# Arduino_MEGA_blank_shield.net
KiCad netlist of a schematic drawn in EAGLE
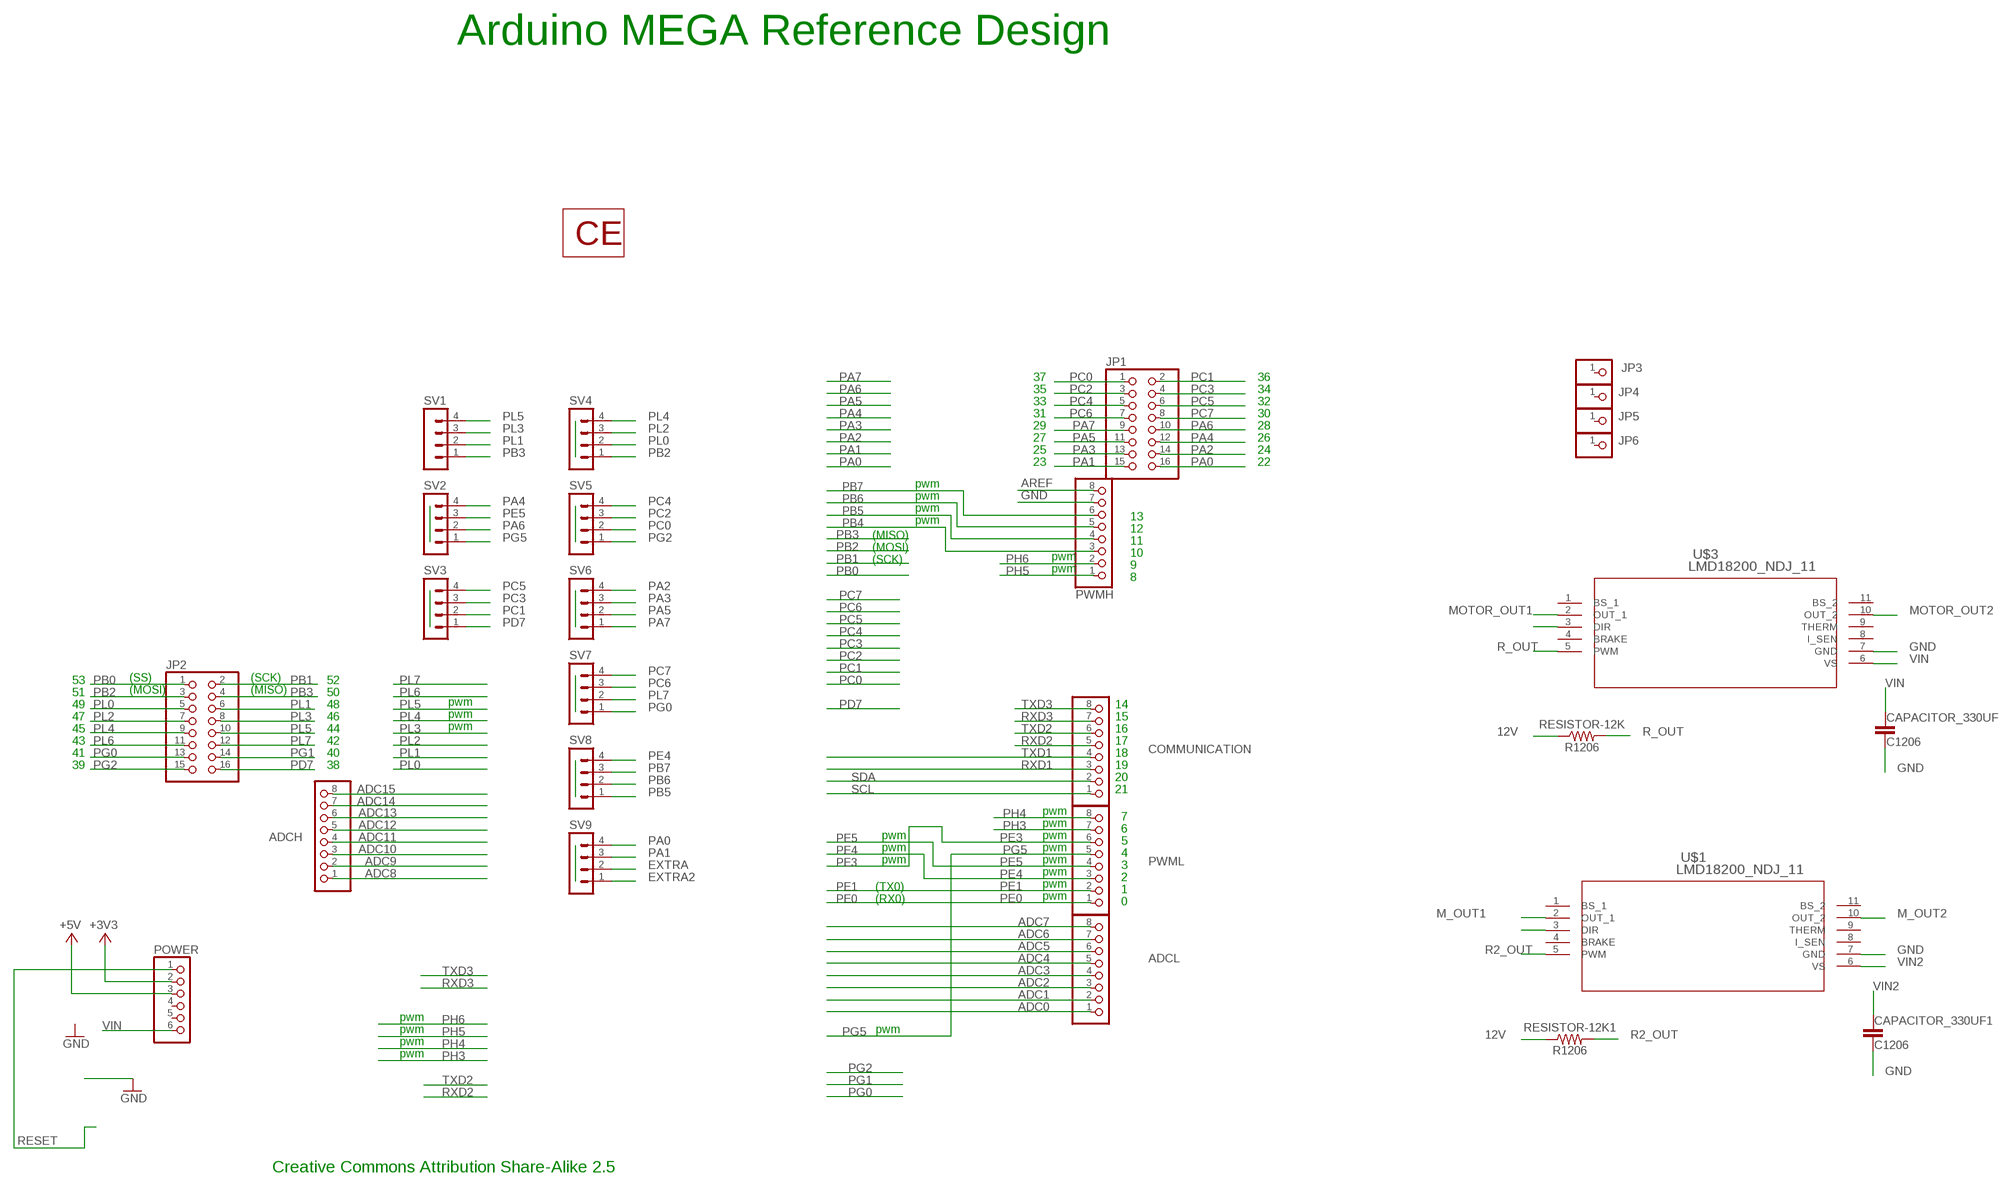
[diagram p0: schematic, sheet 1]

(export (version "E")
  (design (tool "Eeschema 10.0.6"))
  (components
    (comp (ref "ADCH")
      (value "PINHD-1X8")
      (footprint "eagle-import:1X08")
      (libsource (lib "eagle-import") (part "PINHD-1X8"))
    )
    (comp (ref "ADCL")
      (value "PINHD-1X8")
      (footprint "eagle-import:1X08")
      (libsource (lib "eagle-import") (part "PINHD-1X8"))
    )
    (comp (ref "CAPACITOR_330UF")
      (value "C1206")
      (footprint "eagle-import:C1206")
      (libsource (lib "eagle-import") (part "C1206"))
    )
    (comp (ref "CAPACITOR_330UF1")
      (value "C1206")
      (footprint "eagle-import:C1206")
      (libsource (lib "eagle-import") (part "C1206"))
    )
    (comp (ref "COMMUNICATION")
      (value "PINHD-1X8")
      (footprint "eagle-import:1X08")
      (libsource (lib "eagle-import") (part "PINHD-1X8"))
    )
    (comp (ref "JP1")
      (value "PINHD-2X8")
      (footprint "eagle-import:2X08")
      (libsource (lib "eagle-import") (part "PINHD-2X8"))
    )
    (comp (ref "JP2")
      (value "PINHD-2X8")
      (footprint "eagle-import:2X08")
      (libsource (lib "eagle-import") (part "PINHD-2X8"))
    )
    (comp (ref "JP3")
      (value "PINHD-1X1")
      (footprint "eagle-import:1X01")
      (libsource (lib "eagle-import") (part "PINHD-1X1"))
    )
    (comp (ref "JP4")
      (value "PINHD-1X1")
      (footprint "eagle-import:1X01")
      (libsource (lib "eagle-import") (part "PINHD-1X1"))
    )
    (comp (ref "JP5")
      (value "PINHD-1X1")
      (footprint "eagle-import:1X01")
      (libsource (lib "eagle-import") (part "PINHD-1X1"))
    )
    (comp (ref "JP6")
      (value "PINHD-1X1")
      (footprint "eagle-import:1X01")
      (libsource (lib "eagle-import") (part "PINHD-1X1"))
    )
    (comp (ref "POWER")
      (value "PINHD-1X6")
      (footprint "eagle-import:1X06")
      (libsource (lib "eagle-import") (part "PINHD-1X6"))
    )
    (comp (ref "PWMH")
      (value "PINHD-1X8")
      (footprint "eagle-import:1X08")
      (libsource (lib "eagle-import") (part "PINHD-1X8"))
    )
    (comp (ref "PWML")
      (value "PINHD-1X8")
      (footprint "eagle-import:1X08")
      (libsource (lib "eagle-import") (part "PINHD-1X8"))
    )
    (comp (ref "RESISTOR-12K")
      (value "R1206")
      (footprint "eagle-import:R1206")
      (libsource (lib "eagle-import") (part "R1206"))
    )
    (comp (ref "RESISTOR-12K1")
      (value "R1206")
      (footprint "eagle-import:R1206")
      (libsource (lib "eagle-import") (part "R1206"))
    )
    (comp (ref "SV1")
      (value "MA04-1")
      (footprint "eagle-import:MA04-1")
      (libsource (lib "eagle-import") (part "MA04-1"))
    )
    (comp (ref "SV2")
      (value "MA04-1")
      (footprint "eagle-import:MA04-1")
      (libsource (lib "eagle-import") (part "MA04-1"))
    )
    (comp (ref "SV3")
      (value "MA04-1")
      (footprint "eagle-import:MA04-1")
      (libsource (lib "eagle-import") (part "MA04-1"))
    )
    (comp (ref "SV4")
      (value "MA04-1")
      (footprint "eagle-import:MA04-1")
      (libsource (lib "eagle-import") (part "MA04-1"))
    )
    (comp (ref "SV5")
      (value "MA04-1")
      (footprint "eagle-import:MA04-1")
      (libsource (lib "eagle-import") (part "MA04-1"))
    )
    (comp (ref "SV6")
      (value "MA04-1")
      (footprint "eagle-import:MA04-1")
      (libsource (lib "eagle-import") (part "MA04-1"))
    )
    (comp (ref "SV7")
      (value "MA04-1")
      (footprint "eagle-import:MA04-1")
      (libsource (lib "eagle-import") (part "MA04-1"))
    )
    (comp (ref "SV8")
      (value "MA04-1")
      (footprint "eagle-import:MA04-1")
      (libsource (lib "eagle-import") (part "MA04-1"))
    )
    (comp (ref "SV9")
      (value "MA04-1")
      (footprint "eagle-import:MA04-1")
      (libsource (lib "eagle-import") (part "MA04-1"))
    )
    (comp (ref "U$1")
      (value "LMD18200_NDJ_11")
      (footprint "eagle-import:TA11B")
      (fields (field (name "MANUFACTURER_PART_NUMBER") "lmd18200tnopb"))
      (libsource (lib "eagle-import") (part "LMD18200_NDJ_11"))
    )
    (comp (ref "U$3")
      (value "LMD18200_NDJ_11")
      (footprint "eagle-import:TA11B")
      (fields (field (name "MANUFACTURER_PART_NUMBER") "lmd18200tnopb"))
      (libsource (lib "eagle-import") (part "LMD18200_NDJ_11"))
    )
    (comp (ref "U$4")
      (value "CE")
      (footprint "eagle-import:CE-COPPER")
      (libsource (lib "eagle-import") (part "CE"))
    )
  )
  (nets
    (net (code "1") (name "+3V3") (class "Default")
      (node (ref "POWER") (pin "2") (pinfunction "2_2") (pintype "passive"))
    )
    (net (code "2") (name "+5V") (class "Default")
      (node (ref "POWER") (pin "3") (pinfunction "3_3") (pintype "passive"))
    )
    (net (code "3") (name "/12V") (class "Default")
      (node (ref "RESISTOR-12K") (pin "1") (pinfunction "1_1") (pintype "passive"))
      (node (ref "RESISTOR-12K1") (pin "1") (pinfunction "1_1") (pintype "passive"))
    )
    (net (code "4") (name "/ADC0") (class "Default")
      (node (ref "ADCL") (pin "1") (pinfunction "1_1") (pintype "passive"))
    )
    (net (code "5") (name "/ADC1") (class "Default")
      (node (ref "ADCL") (pin "2") (pinfunction "2_2") (pintype "passive"))
    )
    (net (code "6") (name "/ADC2") (class "Default")
      (node (ref "ADCL") (pin "3") (pinfunction "3_3") (pintype "passive"))
    )
    (net (code "7") (name "/ADC3") (class "Default")
      (node (ref "ADCL") (pin "4") (pinfunction "4_4") (pintype "passive"))
    )
    (net (code "8") (name "/ADC4") (class "Default")
      (node (ref "ADCL") (pin "5") (pinfunction "5_5") (pintype "passive"))
    )
    (net (code "9") (name "/ADC5") (class "Default")
      (node (ref "ADCL") (pin "6") (pinfunction "6_6") (pintype "passive"))
    )
    (net (code "10") (name "/ADC6") (class "Default")
      (node (ref "ADCL") (pin "7") (pinfunction "7_7") (pintype "passive"))
    )
    (net (code "11") (name "/ADC7") (class "Default")
      (node (ref "ADCL") (pin "8") (pinfunction "8_8") (pintype "passive"))
    )
    (net (code "12") (name "/ADC8") (class "Default")
      (node (ref "ADCH") (pin "1") (pinfunction "1_1") (pintype "passive"))
    )
    (net (code "13") (name "/ADC9") (class "Default")
      (node (ref "ADCH") (pin "2") (pinfunction "2_2") (pintype "passive"))
    )
    (net (code "14") (name "/ADC10") (class "Default")
      (node (ref "ADCH") (pin "3") (pinfunction "3_3") (pintype "passive"))
    )
    (net (code "15") (name "/ADC11") (class "Default")
      (node (ref "ADCH") (pin "4") (pinfunction "4_4") (pintype "passive"))
    )
    (net (code "16") (name "/ADC12") (class "Default")
      (node (ref "ADCH") (pin "5") (pinfunction "5_5") (pintype "passive"))
    )
    (net (code "17") (name "/ADC13") (class "Default")
      (node (ref "ADCH") (pin "6") (pinfunction "6_6") (pintype "passive"))
    )
    (net (code "18") (name "/ADC14") (class "Default")
      (node (ref "ADCH") (pin "7") (pinfunction "7_7") (pintype "passive"))
    )
    (net (code "19") (name "/ADC15") (class "Default")
      (node (ref "ADCH") (pin "8") (pinfunction "8_8") (pintype "passive"))
    )
    (net (code "20") (name "/AREF") (class "Default")
      (node (ref "PWMH") (pin "8") (pinfunction "8_8") (pintype "passive"))
    )
    (net (code "21") (name "/EXTRA") (class "Default")
      (node (ref "SV9") (pin "2") (pinfunction "2_2") (pintype "passive"))
    )
    (net (code "22") (name "/EXTRA2") (class "Default")
      (node (ref "SV9") (pin "1") (pinfunction "1_1") (pintype "passive"))
    )
    (net (code "23") (name "/MOTOR_OUT1") (class "Default")
      (node (ref "U$3") (pin "2") (pinfunction "OUT_1_2") (pintype "output"))
    )
    (net (code "24") (name "/MOTOR_OUT2") (class "Default")
      (node (ref "U$3") (pin "10") (pinfunction "OUT_2_10") (pintype "output"))
    )
    (net (code "25") (name "/M_OUT1") (class "Default")
      (node (ref "U$1") (pin "2") (pinfunction "OUT_1_2") (pintype "output"))
    )
    (net (code "26") (name "/M_OUT2") (class "Default")
      (node (ref "U$1") (pin "10") (pinfunction "OUT_2_10") (pintype "output"))
    )
    (net (code "27") (name "/PA0") (class "Default")
      (node (ref "JP1") (pin "16") (pinfunction "16_16") (pintype "passive"))
      (node (ref "SV9") (pin "4") (pinfunction "4_4") (pintype "passive"))
    )
    (net (code "28") (name "/PA1") (class "Default")
      (node (ref "JP1") (pin "15") (pinfunction "15_15") (pintype "passive"))
      (node (ref "SV9") (pin "3") (pinfunction "3_3") (pintype "passive"))
    )
    (net (code "29") (name "/PA2") (class "Default")
      (node (ref "JP1") (pin "14") (pinfunction "14_14") (pintype "passive"))
      (node (ref "SV6") (pin "4") (pinfunction "4_4") (pintype "passive"))
    )
    (net (code "30") (name "/PA3") (class "Default")
      (node (ref "JP1") (pin "13") (pinfunction "13_13") (pintype "passive"))
      (node (ref "SV6") (pin "3") (pinfunction "3_3") (pintype "passive"))
    )
    (net (code "31") (name "/PA4") (class "Default")
      (node (ref "JP1") (pin "12") (pinfunction "12_12") (pintype "passive"))
      (node (ref "SV2") (pin "4") (pinfunction "4_4") (pintype "passive"))
    )
    (net (code "32") (name "/PA5") (class "Default")
      (node (ref "JP1") (pin "11") (pinfunction "11_11") (pintype "passive"))
      (node (ref "SV6") (pin "2") (pinfunction "2_2") (pintype "passive"))
    )
    (net (code "33") (name "/PA6") (class "Default")
      (node (ref "JP1") (pin "10") (pinfunction "10_10") (pintype "passive"))
      (node (ref "SV2") (pin "2") (pinfunction "2_2") (pintype "passive"))
    )
    (net (code "34") (name "/PA7") (class "Default")
      (node (ref "JP1") (pin "9") (pinfunction "9_9") (pintype "passive"))
      (node (ref "SV6") (pin "1") (pinfunction "1_1") (pintype "passive"))
    )
    (net (code "35") (name "/PB0") (class "Default")
      (node (ref "JP2") (pin "1") (pinfunction "1_1") (pintype "passive"))
    )
    (net (code "36") (name "/PB1") (class "Default")
      (node (ref "JP2") (pin "2") (pinfunction "2_2") (pintype "passive"))
    )
    (net (code "37") (name "/PB2") (class "Default")
      (node (ref "JP2") (pin "3") (pinfunction "3_3") (pintype "passive"))
      (node (ref "SV4") (pin "1") (pinfunction "1_1") (pintype "passive"))
    )
    (net (code "38") (name "/PB3") (class "Default")
      (node (ref "JP2") (pin "4") (pinfunction "4_4") (pintype "passive"))
      (node (ref "SV1") (pin "1") (pinfunction "1_1") (pintype "passive"))
    )
    (net (code "39") (name "/PB4") (class "Default")
      (node (ref "PWMH") (pin "3") (pinfunction "3_3") (pintype "passive"))
    )
    (net (code "40") (name "/PB5") (class "Default")
      (node (ref "PWMH") (pin "4") (pinfunction "4_4") (pintype "passive"))
      (node (ref "SV8") (pin "1") (pinfunction "1_1") (pintype "passive"))
    )
    (net (code "41") (name "/PB6") (class "Default")
      (node (ref "PWMH") (pin "5") (pinfunction "5_5") (pintype "passive"))
      (node (ref "SV8") (pin "2") (pinfunction "2_2") (pintype "passive"))
    )
    (net (code "42") (name "/PB7") (class "Default")
      (node (ref "PWMH") (pin "6") (pinfunction "6_6") (pintype "passive"))
      (node (ref "SV8") (pin "3") (pinfunction "3_3") (pintype "passive"))
    )
    (net (code "43") (name "/PC0") (class "Default")
      (node (ref "JP1") (pin "1") (pinfunction "1_1") (pintype "passive"))
      (node (ref "SV5") (pin "2") (pinfunction "2_2") (pintype "passive"))
    )
    (net (code "44") (name "/PC1") (class "Default")
      (node (ref "JP1") (pin "2") (pinfunction "2_2") (pintype "passive"))
      (node (ref "SV3") (pin "2") (pinfunction "2_2") (pintype "passive"))
    )
    (net (code "45") (name "/PC2") (class "Default")
      (node (ref "JP1") (pin "3") (pinfunction "3_3") (pintype "passive"))
      (node (ref "SV5") (pin "3") (pinfunction "3_3") (pintype "passive"))
    )
    (net (code "46") (name "/PC3") (class "Default")
      (node (ref "JP1") (pin "4") (pinfunction "4_4") (pintype "passive"))
      (node (ref "SV3") (pin "3") (pinfunction "3_3") (pintype "passive"))
    )
    (net (code "47") (name "/PC4") (class "Default")
      (node (ref "JP1") (pin "5") (pinfunction "5_5") (pintype "passive"))
      (node (ref "SV5") (pin "4") (pinfunction "4_4") (pintype "passive"))
    )
    (net (code "48") (name "/PC5") (class "Default")
      (node (ref "JP1") (pin "6") (pinfunction "6_6") (pintype "passive"))
      (node (ref "SV3") (pin "4") (pinfunction "4_4") (pintype "passive"))
    )
    (net (code "49") (name "/PC6") (class "Default")
      (node (ref "JP1") (pin "7") (pinfunction "7_7") (pintype "passive"))
      (node (ref "SV7") (pin "3") (pinfunction "3_3") (pintype "passive"))
    )
    (net (code "50") (name "/PC7") (class "Default")
      (node (ref "JP1") (pin "8") (pinfunction "8_8") (pintype "passive"))
      (node (ref "SV7") (pin "4") (pinfunction "4_4") (pintype "passive"))
    )
    (net (code "51") (name "/PD7") (class "Default")
      (node (ref "JP2") (pin "16") (pinfunction "16_16") (pintype "passive"))
      (node (ref "SV3") (pin "1") (pinfunction "1_1") (pintype "passive"))
    )
    (net (code "52") (name "/PE0") (class "Default")
      (node (ref "PWML") (pin "1") (pinfunction "1_1") (pintype "passive"))
    )
    (net (code "53") (name "/PE1") (class "Default")
      (node (ref "PWML") (pin "2") (pinfunction "2_2") (pintype "passive"))
    )
    (net (code "54") (name "/PE3") (class "Default")
      (node (ref "PWML") (pin "6") (pinfunction "6_6") (pintype "passive"))
    )
    (net (code "55") (name "/PE4") (class "Default")
      (node (ref "PWML") (pin "3") (pinfunction "3_3") (pintype "passive"))
      (node (ref "SV8") (pin "4") (pinfunction "4_4") (pintype "passive"))
    )
    (net (code "56") (name "/PE5") (class "Default")
      (node (ref "PWML") (pin "4") (pinfunction "4_4") (pintype "passive"))
      (node (ref "SV2") (pin "3") (pinfunction "3_3") (pintype "passive"))
    )
    (net (code "57") (name "/PG0") (class "Default")
      (node (ref "JP2") (pin "13") (pinfunction "13_13") (pintype "passive"))
      (node (ref "SV7") (pin "1") (pinfunction "1_1") (pintype "passive"))
    )
    (net (code "58") (name "/PG1") (class "Default")
      (node (ref "JP2") (pin "14") (pinfunction "14_14") (pintype "passive"))
    )
    (net (code "59") (name "/PG2") (class "Default")
      (node (ref "JP2") (pin "15") (pinfunction "15_15") (pintype "passive"))
      (node (ref "SV5") (pin "1") (pinfunction "1_1") (pintype "passive"))
    )
    (net (code "60") (name "/PG5") (class "Default")
      (node (ref "PWML") (pin "5") (pinfunction "5_5") (pintype "passive"))
      (node (ref "SV2") (pin "1") (pinfunction "1_1") (pintype "passive"))
    )
    (net (code "61") (name "/PH3") (class "Default")
      (node (ref "PWML") (pin "7") (pinfunction "7_7") (pintype "passive"))
    )
    (net (code "62") (name "/PH4") (class "Default")
      (node (ref "PWML") (pin "8") (pinfunction "8_8") (pintype "passive"))
    )
    (net (code "63") (name "/PH5") (class "Default")
      (node (ref "PWMH") (pin "1") (pinfunction "1_1") (pintype "passive"))
    )
    (net (code "64") (name "/PH6") (class "Default")
      (node (ref "PWMH") (pin "2") (pinfunction "2_2") (pintype "passive"))
    )
    (net (code "65") (name "/PL0") (class "Default")
      (node (ref "JP2") (pin "5") (pinfunction "5_5") (pintype "passive"))
      (node (ref "SV4") (pin "2") (pinfunction "2_2") (pintype "passive"))
    )
    (net (code "66") (name "/PL1") (class "Default")
      (node (ref "JP2") (pin "6") (pinfunction "6_6") (pintype "passive"))
      (node (ref "SV1") (pin "2") (pinfunction "2_2") (pintype "passive"))
    )
    (net (code "67") (name "/PL2") (class "Default")
      (node (ref "JP2") (pin "7") (pinfunction "7_7") (pintype "passive"))
      (node (ref "SV4") (pin "3") (pinfunction "3_3") (pintype "passive"))
    )
    (net (code "68") (name "/PL3") (class "Default")
      (node (ref "JP2") (pin "8") (pinfunction "8_8") (pintype "passive"))
      (node (ref "SV1") (pin "3") (pinfunction "3_3") (pintype "passive"))
    )
    (net (code "69") (name "/PL4") (class "Default")
      (node (ref "JP2") (pin "9") (pinfunction "9_9") (pintype "passive"))
      (node (ref "SV4") (pin "4") (pinfunction "4_4") (pintype "passive"))
    )
    (net (code "70") (name "/PL5") (class "Default")
      (node (ref "JP2") (pin "10") (pinfunction "10_10") (pintype "passive"))
      (node (ref "SV1") (pin "4") (pinfunction "4_4") (pintype "passive"))
    )
    (net (code "71") (name "/PL6") (class "Default")
      (node (ref "JP2") (pin "11") (pinfunction "11_11") (pintype "passive"))
    )
    (net (code "72") (name "/PL7") (class "Default")
      (node (ref "JP2") (pin "12") (pinfunction "12_12") (pintype "passive"))
      (node (ref "SV7") (pin "2") (pinfunction "2_2") (pintype "passive"))
    )
    (net (code "73") (name "/R2_OUT") (class "Default")
      (node (ref "RESISTOR-12K1") (pin "2") (pinfunction "2_2") (pintype "passive"))
      (node (ref "U$1") (pin "5") (pinfunction "PWM_5") (pintype "input"))
    )
    (net (code "74") (name "/RESET") (class "Default")
      (node (ref "POWER") (pin "1") (pinfunction "1_1") (pintype "passive"))
    )
    (net (code "75") (name "/RXD1") (class "Default")
      (node (ref "COMMUNICATION") (pin "3") (pinfunction "3_3") (pintype "passive"))
    )
    (net (code "76") (name "/RXD2") (class "Default")
      (node (ref "COMMUNICATION") (pin "5") (pinfunction "5_5") (pintype "passive"))
    )
    (net (code "77") (name "/RXD3") (class "Default")
      (node (ref "COMMUNICATION") (pin "7") (pinfunction "7_7") (pintype "passive"))
    )
    (net (code "78") (name "/R_OUT") (class "Default")
      (node (ref "RESISTOR-12K") (pin "2") (pinfunction "2_2") (pintype "passive"))
      (node (ref "U$3") (pin "5") (pinfunction "PWM_5") (pintype "input"))
    )
    (net (code "79") (name "/SCL") (class "Default")
      (node (ref "COMMUNICATION") (pin "1") (pinfunction "1_1") (pintype "passive"))
    )
    (net (code "80") (name "/SDA") (class "Default")
      (node (ref "COMMUNICATION") (pin "2") (pinfunction "2_2") (pintype "passive"))
    )
    (net (code "81") (name "/TXD1") (class "Default")
      (node (ref "COMMUNICATION") (pin "4") (pinfunction "4_4") (pintype "passive"))
    )
    (net (code "82") (name "/TXD2") (class "Default")
      (node (ref "COMMUNICATION") (pin "6") (pinfunction "6_6") (pintype "passive"))
    )
    (net (code "83") (name "/TXD3") (class "Default")
      (node (ref "COMMUNICATION") (pin "8") (pinfunction "8_8") (pintype "passive"))
    )
    (net (code "84") (name "/VIN") (class "Default")
      (node (ref "CAPACITOR_330UF") (pin "1") (pinfunction "1_1") (pintype "passive"))
      (node (ref "POWER") (pin "6") (pinfunction "6_6") (pintype "passive"))
      (node (ref "U$3") (pin "6") (pinfunction "VS_6") (pintype "power_in"))
    )
    (net (code "85") (name "/VIN2") (class "Default")
      (node (ref "CAPACITOR_330UF1") (pin "1") (pinfunction "1_1") (pintype "passive"))
      (node (ref "U$1") (pin "6") (pinfunction "VS_6") (pintype "power_in"))
    )
    (net (code "86") (name "GND") (class "Default")
      (node (ref "CAPACITOR_330UF") (pin "2") (pinfunction "2_2") (pintype "passive"))
      (node (ref "CAPACITOR_330UF1") (pin "2") (pinfunction "2_2") (pintype "passive"))
      (node (ref "PWMH") (pin "7") (pinfunction "7_7") (pintype "passive"))
      (node (ref "U$1") (pin "7") (pinfunction "GND_7") (pintype "power_in"))
      (node (ref "U$3") (pin "7") (pinfunction "GND_7") (pintype "power_in"))
    )
    (net (code "87") (name "unconnected-(JP3-Pad1)") (class "Default")
      (node (ref "JP3") (pin "1") (pinfunction "1_1") (pintype "passive"))
    )
    (net (code "88") (name "unconnected-(JP4-Pad1)") (class "Default")
      (node (ref "JP4") (pin "1") (pinfunction "1_1") (pintype "passive"))
    )
    (net (code "89") (name "unconnected-(JP5-Pad1)") (class "Default")
      (node (ref "JP5") (pin "1") (pinfunction "1_1") (pintype "passive"))
    )
    (net (code "90") (name "unconnected-(JP6-Pad1)") (class "Default")
      (node (ref "JP6") (pin "1") (pinfunction "1_1") (pintype "passive"))
    )
    (net (code "91") (name "unconnected-(POWER-Pad4)") (class "Default")
      (node (ref "POWER") (pin "4") (pinfunction "4_4") (pintype "passive"))
    )
    (net (code "92") (name "unconnected-(POWER-Pad5)") (class "Default")
      (node (ref "POWER") (pin "5") (pinfunction "5_5") (pintype "passive"))
    )
    (net (code "93") (name "unconnected-(U$1-BRAKE-Pad4)") (class "Default")
      (node (ref "U$1") (pin "4") (pinfunction "BRAKE_4") (pintype "input"))
    )
    (net (code "94") (name "unconnected-(U$1-BS_1-Pad1)") (class "Default")
      (node (ref "U$1") (pin "1") (pinfunction "BS_1_1") (pintype "passive"))
    )
    (net (code "95") (name "unconnected-(U$1-BS_2-Pad11)") (class "Default")
      (node (ref "U$1") (pin "11") (pinfunction "BS_2_11") (pintype "passive"))
    )
    (net (code "96") (name "unconnected-(U$1-DIR-Pad3)") (class "Default")
      (node (ref "U$1") (pin "3") (pinfunction "DIR_3") (pintype "input"))
    )
    (net (code "97") (name "unconnected-(U$1-I_SEN-Pad8)") (class "Default")
      (node (ref "U$1") (pin "8") (pinfunction "I_SEN_8") (pintype "output"))
    )
    (net (code "98") (name "unconnected-(U$1-THERM-Pad9)") (class "Default")
      (node (ref "U$1") (pin "9") (pinfunction "THERM_9") (pintype "output"))
    )
    (net (code "99") (name "unconnected-(U$3-BRAKE-Pad4)") (class "Default")
      (node (ref "U$3") (pin "4") (pinfunction "BRAKE_4") (pintype "input"))
    )
    (net (code "100") (name "unconnected-(U$3-BS_1-Pad1)") (class "Default")
      (node (ref "U$3") (pin "1") (pinfunction "BS_1_1") (pintype "passive"))
    )
    (net (code "101") (name "unconnected-(U$3-BS_2-Pad11)") (class "Default")
      (node (ref "U$3") (pin "11") (pinfunction "BS_2_11") (pintype "passive"))
    )
    (net (code "102") (name "unconnected-(U$3-DIR-Pad3)") (class "Default")
      (node (ref "U$3") (pin "3") (pinfunction "DIR_3") (pintype "input"))
    )
    (net (code "103") (name "unconnected-(U$3-I_SEN-Pad8)") (class "Default")
      (node (ref "U$3") (pin "8") (pinfunction "I_SEN_8") (pintype "output"))
    )
    (net (code "104") (name "unconnected-(U$3-THERM-Pad9)") (class "Default")
      (node (ref "U$3") (pin "9") (pinfunction "THERM_9") (pintype "output"))
    )
  )
)
